# ESP32.net
KiCad netlist of a schematic drawn in EAGLE
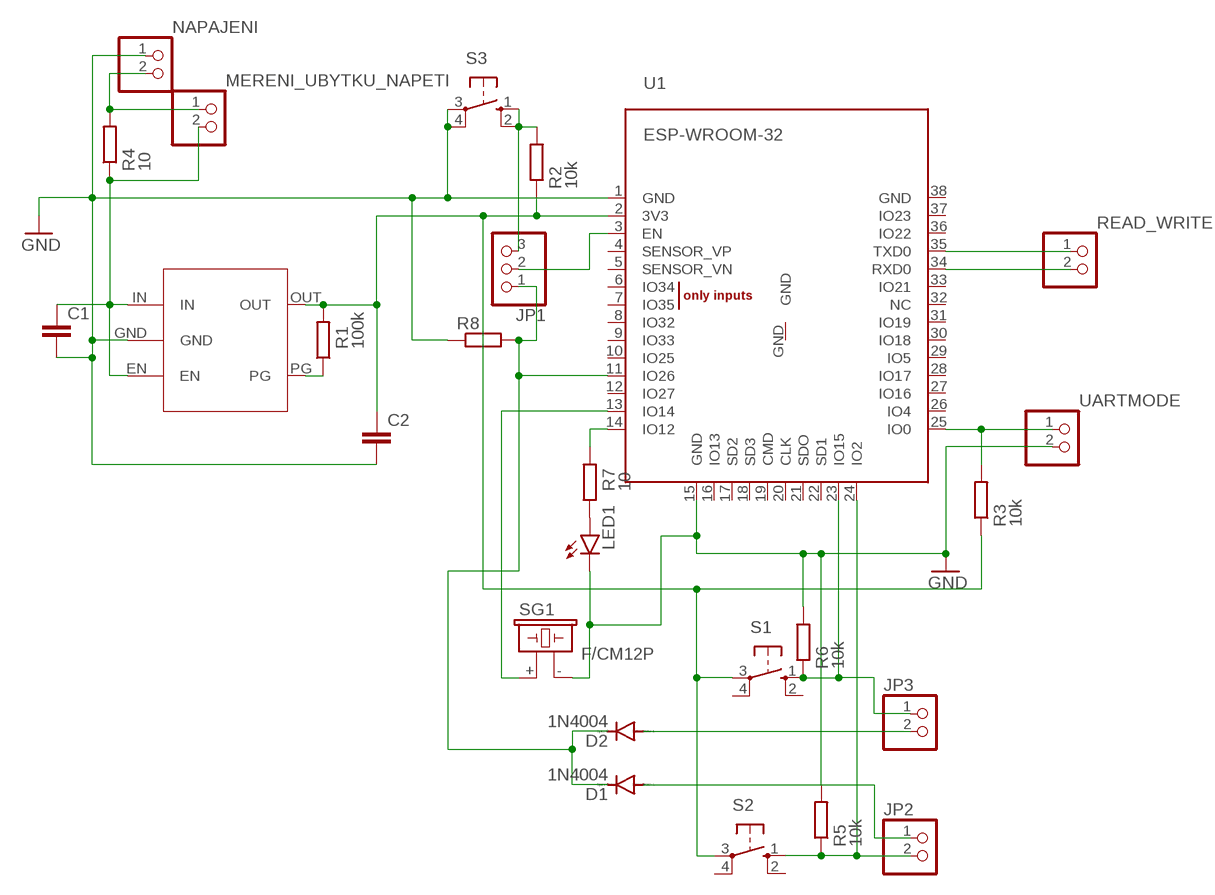
[diagram p0: schematic, sheet 1]

(export (version "E")
  (design (tool "Eeschema 10.0.6"))
  (components
    (comp (ref "C1")
      (value "C2.5/2")
      (footprint "eagle-import:C2.5-2")
      (libsource (lib "eagle-import") (part "C2.5/2"))
    )
    (comp (ref "C2")
      (value "C2.5/2")
      (footprint "eagle-import:C2.5-2")
      (libsource (lib "eagle-import") (part "C2.5/2"))
    )
    (comp (ref "D1")
      (value "1N4004")
      (footprint "eagle-import:DO41-10")
      (libsource (lib "eagle-import") (part "1N4004"))
    )
    (comp (ref "D2")
      (value "1N4004")
      (footprint "eagle-import:DO41-10")
      (libsource (lib "eagle-import") (part "1N4004"))
    )
    (comp (ref "JP1")
      (value "PINHD-1X3")
      (footprint "eagle-import:1X03")
      (libsource (lib "eagle-import") (part "PINHD-1X3"))
    )
    (comp (ref "JP2")
      (value "PINHD-1X2")
      (footprint "eagle-import:1X02")
      (libsource (lib "eagle-import") (part "PINHD-1X2"))
    )
    (comp (ref "JP3")
      (value "PINHD-1X2")
      (footprint "eagle-import:1X02")
      (libsource (lib "eagle-import") (part "PINHD-1X2"))
    )
    (comp (ref "LED1")
      (value "LED5MM")
      (footprint "eagle-import:LED5MM")
      (libsource (lib "eagle-import") (part "LED5MM"))
    )
    (comp (ref "MERENI_UBYTKU_NAPETI")
      (value "PINHD-1X2")
      (footprint "eagle-import:1X02")
      (libsource (lib "eagle-import") (part "PINHD-1X2"))
    )
    (comp (ref "NAPAJENI")
      (value "PINHD-1X2")
      (footprint "eagle-import:1X02")
      (libsource (lib "eagle-import") (part "PINHD-1X2"))
    )
    (comp (ref "R1")
      (value "100k")
      (footprint "eagle-import:0207_10")
      (libsource (lib "eagle-import") (part "R-EU_0207/10"))
    )
    (comp (ref "R2")
      (value "10k")
      (footprint "eagle-import:0207_10")
      (libsource (lib "eagle-import") (part "R-EU_0207/10"))
    )
    (comp (ref "R3")
      (value "10k")
      (footprint "eagle-import:0207_10")
      (libsource (lib "eagle-import") (part "R-EU_0207/10"))
    )
    (comp (ref "R4")
      (value "10")
      (footprint "eagle-import:0207_10")
      (libsource (lib "eagle-import") (part "R-EU_0207/10"))
    )
    (comp (ref "R5")
      (value "10k")
      (footprint "eagle-import:0207_10")
      (libsource (lib "eagle-import") (part "R-EU_0207/10"))
    )
    (comp (ref "R6")
      (value "10k")
      (footprint "eagle-import:0207_10")
      (libsource (lib "eagle-import") (part "R-EU_0207/10"))
    )
    (comp (ref "R7")
      (value "10")
      (footprint "eagle-import:0207_10")
      (libsource (lib "eagle-import") (part "R-EU_0207/10"))
    )
    (comp (ref "R8")
      (value "R-EU_0207/10")
      (footprint "eagle-import:0207_10")
      (libsource (lib "eagle-import") (part "R-EU_0207/10"))
    )
    (comp (ref "READ_WRITE")
      (value "PINHD-1X2")
      (footprint "eagle-import:1X02")
      (libsource (lib "eagle-import") (part "PINHD-1X2"))
    )
    (comp (ref "S1")
      (value "10-XX")
      (footprint "eagle-import:B3F-10XX")
      (fields (field (name "MPN") "B3F-1000"))
      (libsource (lib "eagle-import") (part "10-XX"))
    )
    (comp (ref "S2")
      (value "10-XX")
      (footprint "eagle-import:B3F-10XX")
      (fields (field (name "MPN") "B3F-1000"))
      (libsource (lib "eagle-import") (part "10-XX"))
    )
    (comp (ref "S3")
      (value "10-XX")
      (footprint "eagle-import:B3F-10XX")
      (fields (field (name "MPN") "B3F-1000"))
      (libsource (lib "eagle-import") (part "10-XX"))
    )
    (comp (ref "SG1")
      (value "F/CM12P")
      (footprint "eagle-import:F_CM12P")
      (libsource (lib "eagle-import") (part "F/CM12P"))
    )
    (comp (ref "U$1")
      (value "LDLN030")
      (footprint "eagle-import:LDLN030")
      (libsource (lib "eagle-import") (part "LDLN030"))
    )
    (comp (ref "U1")
      (value "ESP-WROOM-32")
      (footprint "eagle-import:ESP-WROOM-32")
      (libsource (lib "eagle-import") (part "ESP-WROOM-32"))
    )
    (comp (ref "UARTMODE")
      (value "PINHD-1X2")
      (footprint "eagle-import:1X02")
      (libsource (lib "eagle-import") (part "PINHD-1X2"))
    )
  )
  (nets
    (net (code "1") (name "GND") (class "Default")
      (node (ref "C1") (pin "2") (pinfunction "2_2") (pintype "passive"))
      (node (ref "C2") (pin "2") (pinfunction "2_2") (pintype "passive"))
      (node (ref "LED1") (pin "K") (pinfunction "C_K") (pintype "passive"))
      (node (ref "NAPAJENI") (pin "1") (pinfunction "1_1") (pintype "passive"))
      (node (ref "R5") (pin "2") (pinfunction "2_2") (pintype "passive"))
      (node (ref "R6") (pin "2") (pinfunction "2_2") (pintype "passive"))
      (node (ref "R8") (pin "1") (pinfunction "1_1") (pintype "passive"))
      (node (ref "S3") (pin "3") (pinfunction "P_3") (pintype "passive"))
      (node (ref "S3") (pin "4") (pinfunction "P1_4") (pintype "passive"))
      (node (ref "SG1") (pin "-") (pinfunction "2_-") (pintype "passive"))
      (node (ref "U$1") (pin "GND") (pinfunction "GND_GND") (pintype "bidirectional"))
      (node (ref "U1") (pin "1") (pinfunction "GND_1") (pintype "bidirectional"))
      (node (ref "U1") (pin "15") (pinfunction "GND_15") (pintype "bidirectional"))
      (node (ref "UARTMODE") (pin "2") (pinfunction "2_2") (pintype "passive"))
    )
    (net (code "2") (name "Net-(C1-Pad1)") (class "Default")
      (node (ref "C1") (pin "1") (pinfunction "1_1") (pintype "passive"))
      (node (ref "MERENI_UBYTKU_NAPETI") (pin "2") (pinfunction "2_2") (pintype "passive"))
      (node (ref "R4") (pin "1") (pinfunction "1_1") (pintype "passive"))
      (node (ref "U$1") (pin "EN") (pinfunction "EN_EN") (pintype "bidirectional"))
      (node (ref "U$1") (pin "IN") (pinfunction "IN_IN") (pintype "bidirectional"))
    )
    (net (code "3") (name "Net-(D1-PadA)") (class "Default")
      (node (ref "D1") (pin "A") (pinfunction "A_A") (pintype "passive"))
      (node (ref "JP2") (pin "1") (pinfunction "1_1") (pintype "passive"))
    )
    (net (code "4") (name "Net-(D2-PadA)") (class "Default")
      (node (ref "D2") (pin "A") (pinfunction "A_A") (pintype "passive"))
      (node (ref "JP3") (pin "2") (pinfunction "2_2") (pintype "passive"))
    )
    (net (code "5") (name "Net-(LED1-PadA)") (class "Default")
      (node (ref "LED1") (pin "A") (pinfunction "A_A") (pintype "passive"))
      (node (ref "R7") (pin "1") (pinfunction "1_1") (pintype "passive"))
    )
    (net (code "6") (name "Net-(MERENI_UBYTKU_NAPETI-Pad1)") (class "Default")
      (node (ref "MERENI_UBYTKU_NAPETI") (pin "1") (pinfunction "1_1") (pintype "passive"))
      (node (ref "NAPAJENI") (pin "2") (pinfunction "2_2") (pintype "passive"))
      (node (ref "R4") (pin "2") (pinfunction "2_2") (pintype "passive"))
    )
    (net (code "7") (name "Net-(R1-Pad1)") (class "Default")
      (node (ref "R1") (pin "1") (pinfunction "1_1") (pintype "passive"))
      (node (ref "U$1") (pin "PG") (pinfunction "PG_PG") (pintype "bidirectional"))
    )
    (net (code "8") (name "Net-(S1-P)") (class "Default")
      (node (ref "C2") (pin "1") (pinfunction "1_1") (pintype "passive"))
      (node (ref "R1") (pin "2") (pinfunction "2_2") (pintype "passive"))
      (node (ref "R2") (pin "1") (pinfunction "1_1") (pintype "passive"))
      (node (ref "R3") (pin "1") (pinfunction "1_1") (pintype "passive"))
      (node (ref "S1") (pin "3") (pinfunction "P_3") (pintype "passive"))
      (node (ref "S2") (pin "3") (pinfunction "P_3") (pintype "passive"))
      (node (ref "U$1") (pin "OUT") (pinfunction "OUT_OUT") (pintype "bidirectional"))
      (node (ref "U1") (pin "2") (pinfunction "3V3_2") (pintype "bidirectional"))
    )
    (net (code "9") (name "Net-(S1-S)") (class "Default")
      (node (ref "JP3") (pin "1") (pinfunction "1_1") (pintype "passive"))
      (node (ref "R6") (pin "1") (pinfunction "1_1") (pintype "passive"))
      (node (ref "S1") (pin "1") (pinfunction "S_1") (pintype "passive"))
      (node (ref "U1") (pin "23") (pinfunction "IO15_23") (pintype "bidirectional"))
    )
    (net (code "10") (name "Net-(S2-S)") (class "Default")
      (node (ref "JP2") (pin "2") (pinfunction "2_2") (pintype "passive"))
      (node (ref "R5") (pin "1") (pinfunction "1_1") (pintype "passive"))
      (node (ref "S2") (pin "1") (pinfunction "S_1") (pintype "passive"))
      (node (ref "U1") (pin "24") (pinfunction "IO2_24") (pintype "bidirectional"))
    )
    (net (code "11") (name "Net-(S3-S)") (class "Default")
      (node (ref "JP1") (pin "3") (pinfunction "3_3") (pintype "passive"))
      (node (ref "R2") (pin "2") (pinfunction "2_2") (pintype "passive"))
      (node (ref "S3") (pin "1") (pinfunction "S_1") (pintype "passive"))
      (node (ref "S3") (pin "2") (pinfunction "S1_2") (pintype "passive"))
    )
    (net (code "12") (name "Net-(SG1-1)") (class "Default")
      (node (ref "SG1") (pin "+") (pinfunction "1_+") (pintype "passive"))
      (node (ref "U1") (pin "13") (pinfunction "IO14_13") (pintype "bidirectional"))
    )
    (net (code "13") (name "Net-(U1-EN)") (class "Default")
      (node (ref "JP1") (pin "2") (pinfunction "2_2") (pintype "passive"))
      (node (ref "U1") (pin "3") (pinfunction "EN_3") (pintype "bidirectional"))
    )
    (net (code "14") (name "Net-(U1-IO0)") (class "Default")
      (node (ref "R3") (pin "2") (pinfunction "2_2") (pintype "passive"))
      (node (ref "U1") (pin "25") (pinfunction "IO0_25") (pintype "bidirectional"))
      (node (ref "UARTMODE") (pin "1") (pinfunction "1_1") (pintype "passive"))
    )
    (net (code "15") (name "Net-(U1-IO12)") (class "Default")
      (node (ref "R7") (pin "2") (pinfunction "2_2") (pintype "passive"))
      (node (ref "U1") (pin "14") (pinfunction "IO12_14") (pintype "bidirectional"))
    )
    (net (code "16") (name "Net-(U1-IO26)") (class "Default")
      (node (ref "D1") (pin "C") (pinfunction "C_C") (pintype "passive"))
      (node (ref "D2") (pin "C") (pinfunction "C_C") (pintype "passive"))
      (node (ref "JP1") (pin "1") (pinfunction "1_1") (pintype "passive"))
      (node (ref "R8") (pin "2") (pinfunction "2_2") (pintype "passive"))
      (node (ref "U1") (pin "11") (pinfunction "IO26_11") (pintype "bidirectional"))
    )
    (net (code "17") (name "Net-(U1-RXD0)") (class "Default")
      (node (ref "READ_WRITE") (pin "2") (pinfunction "2_2") (pintype "passive"))
      (node (ref "U1") (pin "34") (pinfunction "RXD0_34") (pintype "bidirectional"))
    )
    (net (code "18") (name "Net-(U1-TXD0)") (class "Default")
      (node (ref "READ_WRITE") (pin "1") (pinfunction "1_1") (pintype "passive"))
      (node (ref "U1") (pin "35") (pinfunction "TXD0_35") (pintype "bidirectional"))
    )
    (net (code "19") (name "unconnected-(S1-P1-Pad4)") (class "Default")
      (node (ref "S1") (pin "4") (pinfunction "P1_4") (pintype "passive"))
    )
    (net (code "20") (name "unconnected-(S1-S1-Pad2)") (class "Default")
      (node (ref "S1") (pin "2") (pinfunction "S1_2") (pintype "passive"))
    )
    (net (code "21") (name "unconnected-(S2-P1-Pad4)") (class "Default")
      (node (ref "S2") (pin "4") (pinfunction "P1_4") (pintype "passive"))
    )
    (net (code "22") (name "unconnected-(S2-S1-Pad2)") (class "Default")
      (node (ref "S2") (pin "2") (pinfunction "S1_2") (pintype "passive"))
    )
    (net (code "23") (name "unconnected-(U1-CLK-Pad20)") (class "Default")
      (node (ref "U1") (pin "20") (pinfunction "CLK_20") (pintype "bidirectional"))
    )
    (net (code "24") (name "unconnected-(U1-CMD-Pad19)") (class "Default")
      (node (ref "U1") (pin "19") (pinfunction "CMD_19") (pintype "bidirectional"))
    )
    (net (code "25") (name "unconnected-(U1-GND-Pad38)") (class "Default")
      (node (ref "U1") (pin "38") (pinfunction "GND_38") (pintype "bidirectional"))
    )
    (net (code "26") (name "unconnected-(U1-IO4-Pad26)") (class "Default")
      (node (ref "U1") (pin "26") (pinfunction "IO4_26") (pintype "bidirectional"))
    )
    (net (code "27") (name "unconnected-(U1-IO5-Pad29)") (class "Default")
      (node (ref "U1") (pin "29") (pinfunction "IO5_29") (pintype "bidirectional"))
    )
    (net (code "28") (name "unconnected-(U1-IO13-Pad16)") (class "Default")
      (node (ref "U1") (pin "16") (pinfunction "IO13_16") (pintype "bidirectional"))
    )
    (net (code "29") (name "unconnected-(U1-IO16-Pad27)") (class "Default")
      (node (ref "U1") (pin "27") (pinfunction "IO16_27") (pintype "bidirectional"))
    )
    (net (code "30") (name "unconnected-(U1-IO17-Pad28)") (class "Default")
      (node (ref "U1") (pin "28") (pinfunction "IO17_28") (pintype "bidirectional"))
    )
    (net (code "31") (name "unconnected-(U1-IO18-Pad30)") (class "Default")
      (node (ref "U1") (pin "30") (pinfunction "IO18_30") (pintype "bidirectional"))
    )
    (net (code "32") (name "unconnected-(U1-IO19-Pad31)") (class "Default")
      (node (ref "U1") (pin "31") (pinfunction "IO19_31") (pintype "bidirectional"))
    )
    (net (code "33") (name "unconnected-(U1-IO21-Pad33)") (class "Default")
      (node (ref "U1") (pin "33") (pinfunction "IO21_33") (pintype "bidirectional"))
    )
    (net (code "34") (name "unconnected-(U1-IO22-Pad36)") (class "Default")
      (node (ref "U1") (pin "36") (pinfunction "IO22_36") (pintype "bidirectional"))
    )
    (net (code "35") (name "unconnected-(U1-IO23-Pad37)") (class "Default")
      (node (ref "U1") (pin "37") (pinfunction "IO23_37") (pintype "bidirectional"))
    )
    (net (code "36") (name "unconnected-(U1-IO25-Pad10)") (class "Default")
      (node (ref "U1") (pin "10") (pinfunction "IO25_10") (pintype "bidirectional"))
    )
    (net (code "37") (name "unconnected-(U1-IO27-Pad12)") (class "Default")
      (node (ref "U1") (pin "12") (pinfunction "IO27_12") (pintype "bidirectional"))
    )
    (net (code "38") (name "unconnected-(U1-IO32-Pad8)") (class "Default")
      (node (ref "U1") (pin "8") (pinfunction "IO32_8") (pintype "bidirectional"))
    )
    (net (code "39") (name "unconnected-(U1-IO33-Pad9)") (class "Default")
      (node (ref "U1") (pin "9") (pinfunction "IO33_9") (pintype "bidirectional"))
    )
    (net (code "40") (name "unconnected-(U1-IO34-Pad6)") (class "Default")
      (node (ref "U1") (pin "6") (pinfunction "IO34_6") (pintype "input"))
    )
    (net (code "41") (name "unconnected-(U1-IO35-Pad7)") (class "Default")
      (node (ref "U1") (pin "7") (pinfunction "IO35_7") (pintype "input"))
    )
    (net (code "42") (name "unconnected-(U1-NC-Pad32)") (class "Default")
      (node (ref "U1") (pin "32") (pinfunction "NC_32") (pintype "bidirectional"))
    )
    (net (code "43") (name "unconnected-(U1-PadGND)") (class "Default")
      (node (ref "U1") (pin "GND") (pinfunction "GND_GND") (pintype "bidirectional"))
    )
    (net (code "44") (name "unconnected-(U1-SD1-Pad22)") (class "Default")
      (node (ref "U1") (pin "22") (pinfunction "SD1_22") (pintype "bidirectional"))
    )
    (net (code "45") (name "unconnected-(U1-SD2-Pad17)") (class "Default")
      (node (ref "U1") (pin "17") (pinfunction "SD2_17") (pintype "bidirectional"))
    )
    (net (code "46") (name "unconnected-(U1-SD3-Pad18)") (class "Default")
      (node (ref "U1") (pin "18") (pinfunction "SD3_18") (pintype "bidirectional"))
    )
    (net (code "47") (name "unconnected-(U1-SDO-Pad21)") (class "Default")
      (node (ref "U1") (pin "21") (pinfunction "SDO_21") (pintype "bidirectional"))
    )
    (net (code "48") (name "unconnected-(U1-SENSOR_VN-Pad5)") (class "Default")
      (node (ref "U1") (pin "5") (pinfunction "SENSOR_VN_5") (pintype "input"))
    )
    (net (code "49") (name "unconnected-(U1-SENSOR_VP-Pad4)") (class "Default")
      (node (ref "U1") (pin "4") (pinfunction "SENSOR_VP_4") (pintype "input"))
    )
  )
)
